# MPU9250-IMU_I2C_V1.net
KiCad netlist of a schematic drawn in EAGLE
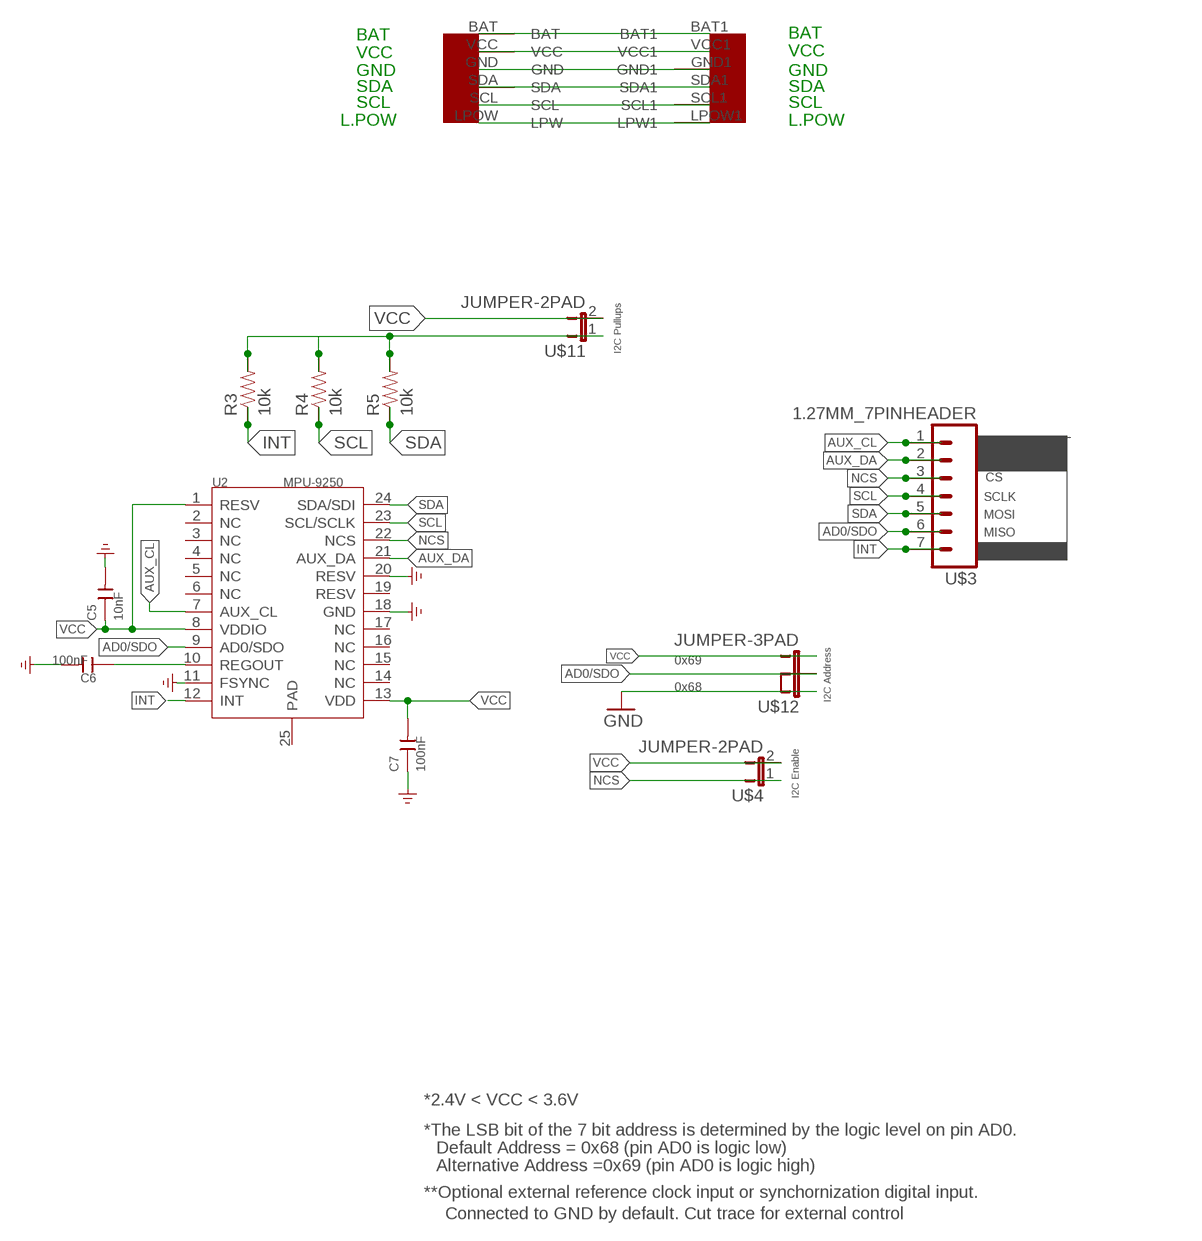
[diagram p0: schematic, sheet 1]

(export (version "E")
  (design (tool "Eeschema 10.0.6"))
  (components
    (comp (ref "C5")
      (value "10nF")
      (footprint "eagle-import:C0603")
      (libsource (lib "eagle-import") (part "CAP-0603"))
    )
    (comp (ref "C6")
      (value "100nF")
      (footprint "eagle-import:C0603")
      (libsource (lib "eagle-import") (part "CAP-0603"))
    )
    (comp (ref "C7")
      (value "100nF")
      (footprint "eagle-import:C0603")
      (libsource (lib "eagle-import") (part "CAP-0603"))
    )
    (comp (ref "R3")
      (value "10k")
      (footprint "eagle-import:0402-RES")
      (libsource (lib "eagle-import") (part "RESISTOR0402-RES"))
    )
    (comp (ref "R4")
      (value "10k")
      (footprint "eagle-import:0402-RES")
      (libsource (lib "eagle-import") (part "RESISTOR0402-RES"))
    )
    (comp (ref "R5")
      (value "10k")
      (footprint "eagle-import:0402-RES")
      (libsource (lib "eagle-import") (part "RESISTOR0402-RES"))
    )
    (comp (ref "U$1")
      (value "EZ-I2CHEADERV1")
      (footprint "eagle-import:EZ-I2CHEADERV1")
      (libsource (lib "eagle-import") (part "EZ-I2CHEADERV1"))
    )
    (comp (ref "U$3")
      (value "1.27MM_7PINHEADER")
      (footprint "eagle-import:1.27MM_7PINHEADER")
      (libsource (lib "eagle-import") (part "1.27MM_7PINHEADER"))
    )
    (comp (ref "U$4")
      (value "JUMPER-2PAD")
      (footprint "eagle-import:JUMPER-2PAD")
      (libsource (lib "eagle-import") (part "JUMPER-2PAD"))
    )
    (comp (ref "U$11")
      (value "JUMPER-2PAD")
      (footprint "eagle-import:JUMPER-2PAD")
      (libsource (lib "eagle-import") (part "JUMPER-2PAD"))
    )
    (comp (ref "U$12")
      (value "JUMPER-3PAD")
      (footprint "eagle-import:JUMPER-3PAD")
      (libsource (lib "eagle-import") (part "JUMPER-3PAD"))
    )
    (comp (ref "U2")
      (value "MPU-9250")
      (footprint "eagle-import:LEAD-QFN24")
      (libsource (lib "eagle-import") (part "MPU-9250"))
    )
  )
  (nets
    (net (code "1") (name "AD0{slash}SDO") (class "Default")
      (node (ref "U$12") (pin "2") (pinfunction "2_2") (pintype "passive"))
      (node (ref "U$3") (pin "6") (pinfunction "6_6") (pintype "passive"))
      (node (ref "U2") (pin "9") (pinfunction "AD0/SDO_9") (pintype "bidirectional"))
    )
    (net (code "2") (name "AUX_CL") (class "Default")
      (node (ref "U$3") (pin "1") (pinfunction "1_1") (pintype "passive"))
      (node (ref "U2") (pin "7") (pinfunction "AUX_CL_7") (pintype "bidirectional"))
    )
    (net (code "3") (name "AUX_DA") (class "Default")
      (node (ref "U$3") (pin "2") (pinfunction "2_2") (pintype "passive"))
      (node (ref "U2") (pin "21") (pinfunction "AUX_DA_21") (pintype "bidirectional"))
    )
    (net (code "4") (name "GND") (class "Default")
      (node (ref "C5") (pin "2") (pinfunction "2_2") (pintype "passive"))
      (node (ref "C6") (pin "2") (pinfunction "2_2") (pintype "passive"))
      (node (ref "C7") (pin "1") (pinfunction "1_1") (pintype "passive"))
      (node (ref "U$1") (pin "GND") (pinfunction "GND_GND") (pintype "bidirectional"))
      (node (ref "U$1") (pin "GND1") (pinfunction "GND1_GND1") (pintype "bidirectional"))
      (node (ref "U$12") (pin "1") (pinfunction "1_1") (pintype "passive"))
      (node (ref "U2") (pin "11") (pinfunction "FSYNC_11") (pintype "bidirectional"))
      (node (ref "U2") (pin "18") (pinfunction "GND_18") (pintype "bidirectional"))
      (node (ref "U2") (pin "20") (pinfunction "RESV_20") (pintype "bidirectional"))
    )
    (net (code "5") (name "INT") (class "Default")
      (node (ref "R3") (pin "1") (pinfunction "1_1") (pintype "passive"))
      (node (ref "U$3") (pin "7") (pinfunction "7_7") (pintype "passive"))
      (node (ref "U2") (pin "12") (pinfunction "INT_12") (pintype "bidirectional"))
    )
    (net (code "6") (name "NCS") (class "Default")
      (node (ref "U$3") (pin "3") (pinfunction "3_3") (pintype "passive"))
      (node (ref "U$4") (pin "1") (pinfunction "1_1") (pintype "passive"))
      (node (ref "U2") (pin "22") (pinfunction "NCS_22") (pintype "bidirectional"))
    )
    (net (code "7") (name "Net-(R3-Pad2)") (class "Default")
      (node (ref "R3") (pin "2") (pinfunction "2_2") (pintype "passive"))
      (node (ref "R4") (pin "2") (pinfunction "2_2") (pintype "passive"))
      (node (ref "R5") (pin "2") (pinfunction "2_2") (pintype "passive"))
      (node (ref "U$11") (pin "1") (pinfunction "1_1") (pintype "passive"))
    )
    (net (code "8") (name "Net-(U$1-LPW)") (class "Default")
      (node (ref "U$1") (pin "LPOW") (pinfunction "LPW_LPOW") (pintype "bidirectional"))
      (node (ref "U$1") (pin "LPOW1") (pinfunction "LPW1_LPOW1") (pintype "bidirectional"))
    )
    (net (code "9") (name "Net-(U$1-PadBAT)") (class "Default")
      (node (ref "U$1") (pin "BAT") (pinfunction "BAT_BAT") (pintype "bidirectional"))
      (node (ref "U$1") (pin "BAT1") (pinfunction "BAT1_BAT1") (pintype "bidirectional"))
    )
    (net (code "10") (name "Net-(U2-REGOUT)") (class "Default")
      (node (ref "C6") (pin "1") (pinfunction "1_1") (pintype "passive"))
      (node (ref "U2") (pin "10") (pinfunction "REGOUT_10") (pintype "bidirectional"))
    )
    (net (code "11") (name "SCL") (class "Default")
      (node (ref "R4") (pin "1") (pinfunction "1_1") (pintype "passive"))
      (node (ref "U$1") (pin "SCL") (pinfunction "SCL_SCL") (pintype "bidirectional"))
      (node (ref "U$1") (pin "SCL1") (pinfunction "SCL1_SCL1") (pintype "bidirectional"))
      (node (ref "U$3") (pin "4") (pinfunction "4_4") (pintype "passive"))
      (node (ref "U2") (pin "23") (pinfunction "SCL/SCLK_23") (pintype "bidirectional"))
    )
    (net (code "12") (name "SDA") (class "Default")
      (node (ref "R5") (pin "1") (pinfunction "1_1") (pintype "passive"))
      (node (ref "U$1") (pin "SDA") (pinfunction "SDA_SDA") (pintype "bidirectional"))
      (node (ref "U$1") (pin "SDA1") (pinfunction "SDA1_SDA1") (pintype "bidirectional"))
      (node (ref "U$3") (pin "5") (pinfunction "5_5") (pintype "passive"))
      (node (ref "U2") (pin "24") (pinfunction "SDA/SDI_24") (pintype "bidirectional"))
    )
    (net (code "13") (name "VCC") (class "Default")
      (node (ref "C5") (pin "1") (pinfunction "1_1") (pintype "passive"))
      (node (ref "C7") (pin "2") (pinfunction "2_2") (pintype "passive"))
      (node (ref "U$1") (pin "VCC") (pinfunction "VCC_VCC") (pintype "bidirectional"))
      (node (ref "U$1") (pin "VCC1") (pinfunction "VCC1_VCC1") (pintype "bidirectional"))
      (node (ref "U$11") (pin "2") (pinfunction "2_2") (pintype "passive"))
      (node (ref "U$12") (pin "3") (pinfunction "3_3") (pintype "passive"))
      (node (ref "U$4") (pin "2") (pinfunction "2_2") (pintype "passive"))
      (node (ref "U2") (pin "1") (pinfunction "RESV_1") (pintype "bidirectional"))
      (node (ref "U2") (pin "13") (pinfunction "VDD_13") (pintype "bidirectional"))
      (node (ref "U2") (pin "8") (pinfunction "VDDIO_8") (pintype "bidirectional"))
    )
    (net (code "14") (name "unconnected-(U2-NC-Pad2)") (class "Default")
      (node (ref "U2") (pin "2") (pinfunction "NC_2") (pintype "bidirectional"))
    )
    (net (code "15") (name "unconnected-(U2-NC-Pad3)") (class "Default")
      (node (ref "U2") (pin "3") (pinfunction "NC_3") (pintype "bidirectional"))
    )
    (net (code "16") (name "unconnected-(U2-NC-Pad4)") (class "Default")
      (node (ref "U2") (pin "4") (pinfunction "NC_4") (pintype "bidirectional"))
    )
    (net (code "17") (name "unconnected-(U2-NC-Pad5)") (class "Default")
      (node (ref "U2") (pin "5") (pinfunction "NC_5") (pintype "bidirectional"))
    )
    (net (code "18") (name "unconnected-(U2-NC-Pad6)") (class "Default")
      (node (ref "U2") (pin "6") (pinfunction "NC_6") (pintype "bidirectional"))
    )
    (net (code "19") (name "unconnected-(U2-NC-Pad14)") (class "Default")
      (node (ref "U2") (pin "14") (pinfunction "NC_14") (pintype "bidirectional"))
    )
    (net (code "20") (name "unconnected-(U2-NC-Pad15)") (class "Default")
      (node (ref "U2") (pin "15") (pinfunction "NC_15") (pintype "bidirectional"))
    )
    (net (code "21") (name "unconnected-(U2-NC-Pad16)") (class "Default")
      (node (ref "U2") (pin "16") (pinfunction "NC_16") (pintype "bidirectional"))
    )
    (net (code "22") (name "unconnected-(U2-NC-Pad17)") (class "Default")
      (node (ref "U2") (pin "17") (pinfunction "NC_17") (pintype "bidirectional"))
    )
    (net (code "23") (name "unconnected-(U2-PAD-Pad25)") (class "Default")
      (node (ref "U2") (pin "25") (pinfunction "PAD_25") (pintype "bidirectional"))
    )
    (net (code "24") (name "unconnected-(U2-RESV-Pad19)") (class "Default")
      (node (ref "U2") (pin "19") (pinfunction "RESV_19") (pintype "bidirectional"))
    )
  )
)
